# atum.net
KiCad netlist of a schematic drawn in EAGLE
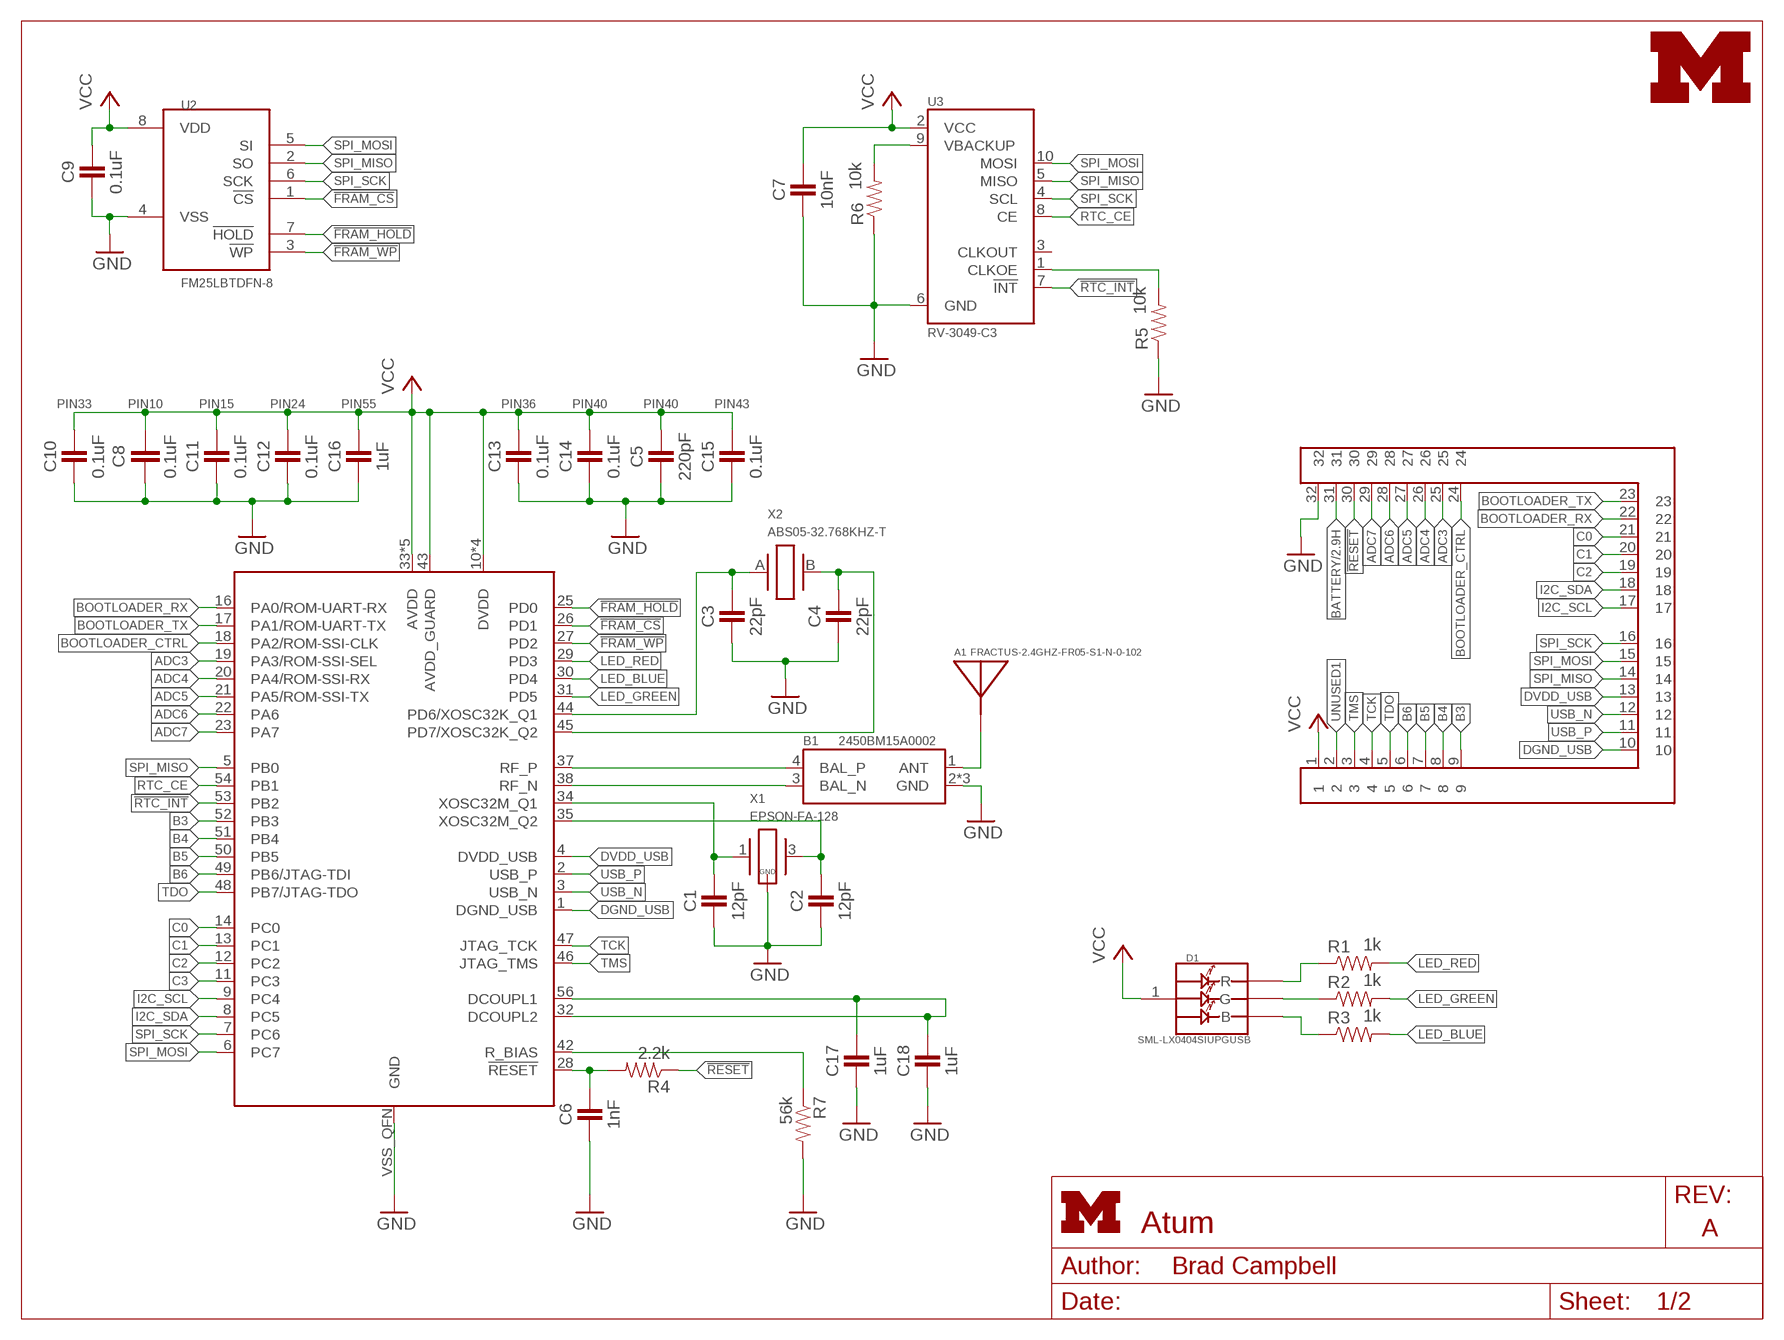
[diagram p0: schematic, sheet 1]
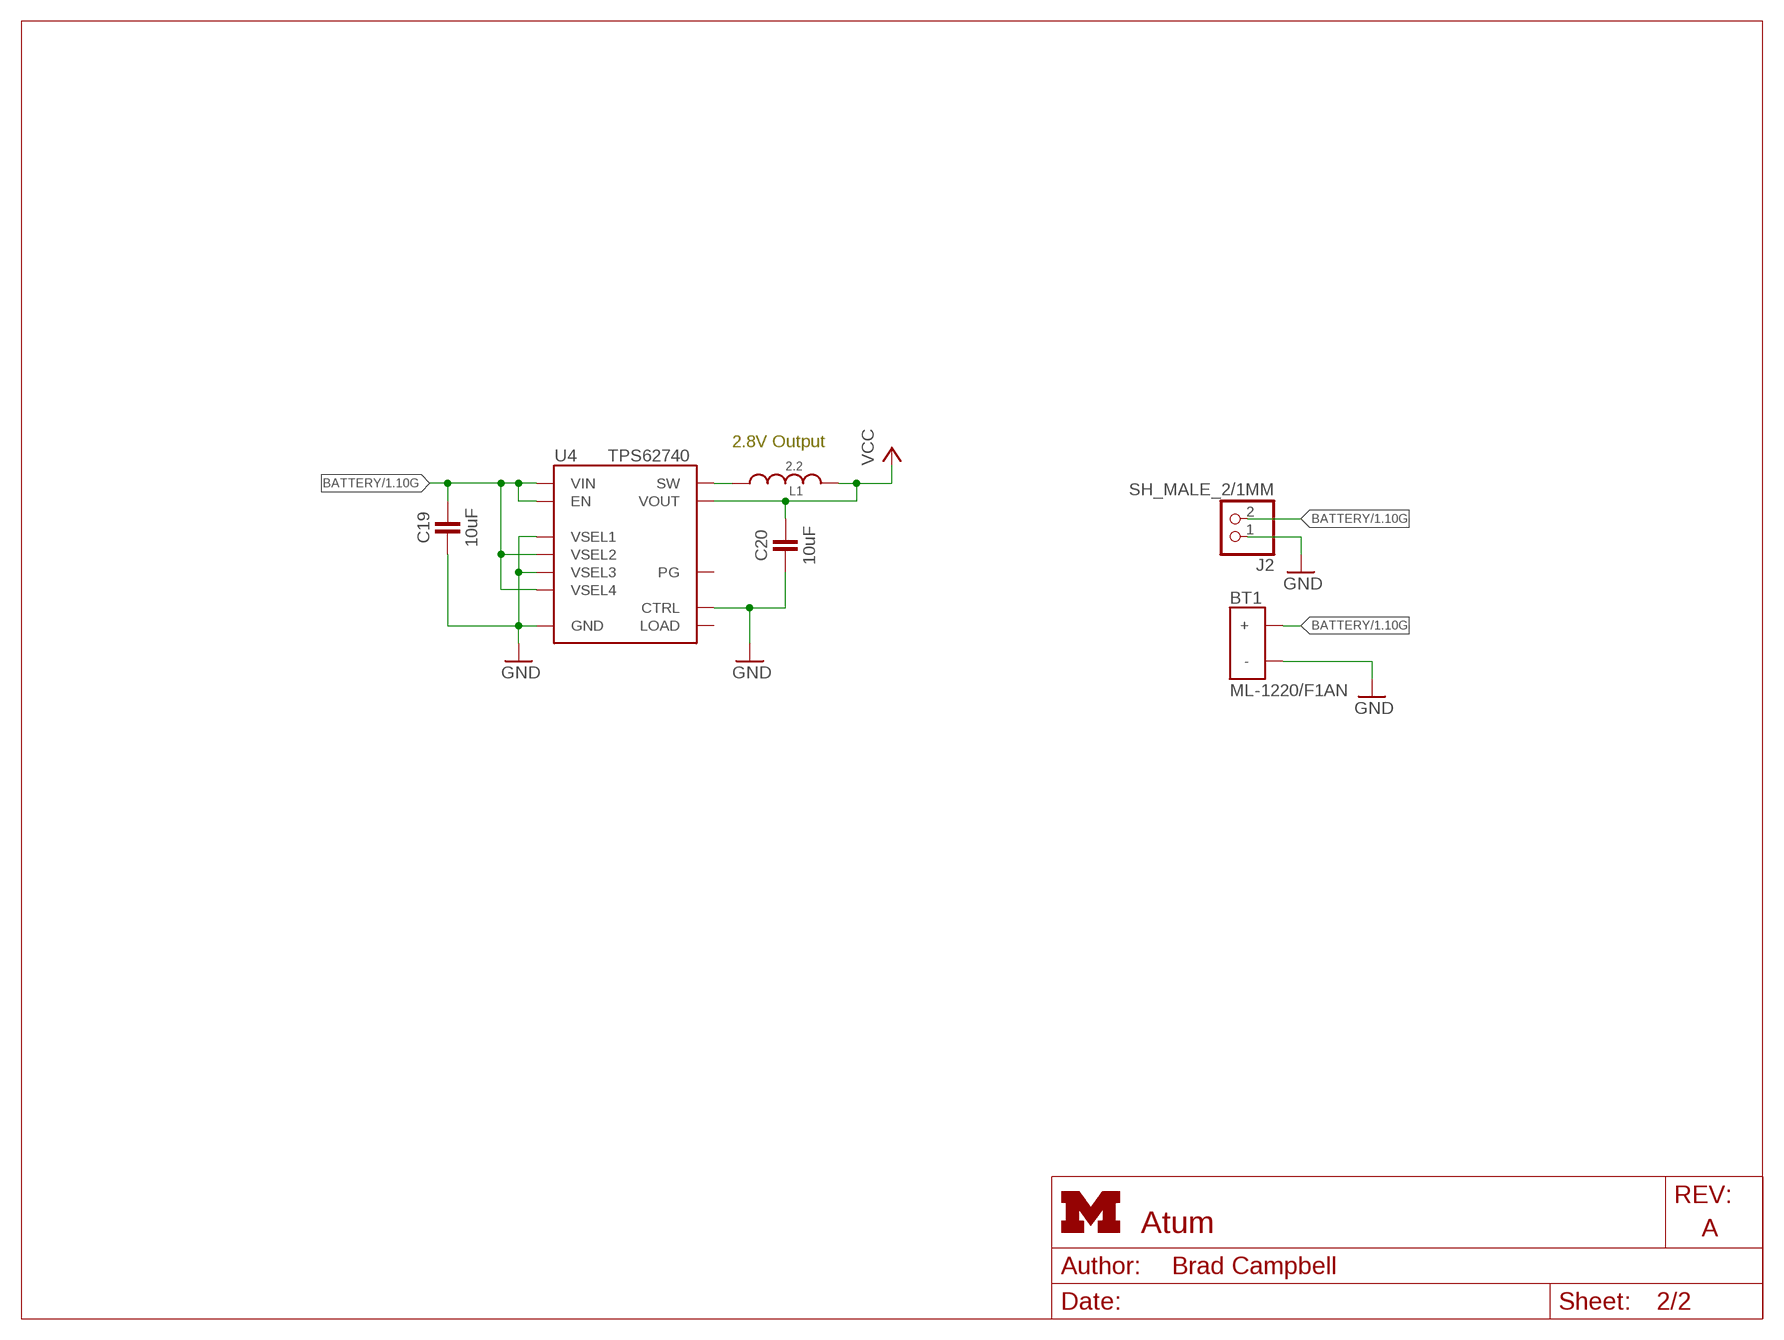
[diagram p1: schematic, sheet 2]

(export (version "E")
  (design (tool "Eeschema 10.0.6"))
  (components
    (comp (ref "A1")
      (value "FRACTUS-2.4GHZ-FR05-S1-N-0-102")
      (footprint "eagle-import:FRACTUS-ANTENNA-FR05-S1-N-0-102")
      (libsource (lib "eagle-import") (part "FRACTUS-2.4GHZ-FR05-S1-N-0-102"))
    )
    (comp (ref "B1")
      (value "2450BM15A0002")
      (footprint "eagle-import:2450BM")
      (libsource (lib "eagle-import") (part "2450BM15A0002"))
    )
    (comp (ref "C1")
      (value "12pF")
      (footprint "eagle-import:0402_CAP")
      (libsource (lib "eagle-import") (part "CAPACITOR"))
    )
    (comp (ref "C2")
      (value "12pF")
      (footprint "eagle-import:0402_CAP")
      (libsource (lib "eagle-import") (part "CAPACITOR"))
    )
    (comp (ref "C3")
      (value "22pF")
      (footprint "eagle-import:0402_CAP")
      (libsource (lib "eagle-import") (part "CAPACITOR"))
    )
    (comp (ref "C4")
      (value "22pF")
      (footprint "eagle-import:0402_CAP")
      (libsource (lib "eagle-import") (part "CAPACITOR"))
    )
    (comp (ref "C5")
      (value "220pF")
      (footprint "eagle-import:0402_CAP")
      (libsource (lib "eagle-import") (part "CAPACITOR"))
    )
    (comp (ref "C6")
      (value "1nF")
      (footprint "eagle-import:0402_CAP")
      (libsource (lib "eagle-import") (part "CAPACITOR"))
    )
    (comp (ref "C7")
      (value "10nF")
      (footprint "eagle-import:0402_CAP")
      (libsource (lib "eagle-import") (part "CAPACITOR"))
    )
    (comp (ref "C8")
      (value "0.1uF")
      (footprint "eagle-import:C0201")
      (libsource (lib "eagle-import") (part "C-EUC0201"))
    )
    (comp (ref "C9")
      (value "0.1uF")
      (footprint "eagle-import:0402_CAP")
      (libsource (lib "eagle-import") (part "CAPACITOR"))
    )
    (comp (ref "C10")
      (value "0.1uF")
      (footprint "eagle-import:0402_CAP")
      (libsource (lib "eagle-import") (part "CAPACITOR"))
    )
    (comp (ref "C11")
      (value "0.1uF")
      (footprint "eagle-import:0402_CAP")
      (libsource (lib "eagle-import") (part "CAPACITOR"))
    )
    (comp (ref "C12")
      (value "0.1uF")
      (footprint "eagle-import:0402_CAP")
      (libsource (lib "eagle-import") (part "CAPACITOR"))
    )
    (comp (ref "C13")
      (value "0.1uF")
      (footprint "eagle-import:0402_CAP")
      (libsource (lib "eagle-import") (part "CAPACITOR"))
    )
    (comp (ref "C14")
      (value "0.1uF")
      (footprint "eagle-import:0402_CAP")
      (libsource (lib "eagle-import") (part "CAPACITOR"))
    )
    (comp (ref "C15")
      (value "0.1uF")
      (footprint "eagle-import:0402_CAP")
      (libsource (lib "eagle-import") (part "CAPACITOR"))
    )
    (comp (ref "C16")
      (value "1uF")
      (footprint "eagle-import:0402_CAP")
      (libsource (lib "eagle-import") (part "CAPACITOR"))
    )
    (comp (ref "C17")
      (value "1uF")
      (footprint "eagle-import:0402_CAP")
      (libsource (lib "eagle-import") (part "CAPACITOR"))
    )
    (comp (ref "C18")
      (value "1uF")
      (footprint "eagle-import:0402_CAP")
      (libsource (lib "eagle-import") (part "CAPACITOR"))
    )
    (comp (ref "D1")
      (value "SML-LX0404SIUPGUSB")
      (footprint "eagle-import:1MM_SQ_4PAD")
      (libsource (lib "eagle-import") (part "SML-LX0404SIUPGUSB"))
    )
    (comp (ref "J1")
      (value "EPIC2-HEADER2")
      (footprint "eagle-import:EPIC2-HEADER2")
      (libsource (lib "eagle-import") (part "EPIC2-HEADER2"))
    )
    (comp (ref "LOGO1")
      (value "UMICH_SOLID_TINY")
      (footprint "eagle-import:UMICH_SOLID_50MIL")
      (libsource (lib "eagle-import") (part "UMICH_SOLID_TINY"))
    )
    (comp (ref "R1")
      (value "1k")
      (footprint "eagle-import:0402_RES")
      (libsource (lib "eagle-import") (part "RESISTOR"))
    )
    (comp (ref "R2")
      (value "1k")
      (footprint "eagle-import:0402_RES")
      (libsource (lib "eagle-import") (part "RESISTOR"))
    )
    (comp (ref "R3")
      (value "1k")
      (footprint "eagle-import:0402_RES")
      (libsource (lib "eagle-import") (part "RESISTOR"))
    )
    (comp (ref "R4")
      (value "2.2k")
      (footprint "eagle-import:0402_RES")
      (libsource (lib "eagle-import") (part "RESISTOR"))
    )
    (comp (ref "R5")
      (value "10k")
      (footprint "eagle-import:0402_RES")
      (libsource (lib "eagle-import") (part "RESISTOR"))
    )
    (comp (ref "R6")
      (value "10k")
      (footprint "eagle-import:0402_RES")
      (libsource (lib "eagle-import") (part "RESISTOR"))
    )
    (comp (ref "R7")
      (value "56k")
      (footprint "eagle-import:0402_RES")
      (libsource (lib "eagle-import") (part "RESISTOR"))
    )
    (comp (ref "U1")
      (value "CC2538")
      (footprint "eagle-import:S-PVQFN-N56")
      (libsource (lib "eagle-import") (part "CC2538"))
    )
    (comp (ref "U2")
      (value "FM25LBTDFN-8")
      (footprint "eagle-import:TDFN-8")
      (libsource (lib "eagle-import") (part "FM25LBTDFN-8"))
    )
    (comp (ref "U3")
      (value "RV-3049-C3")
      (footprint "eagle-import:MICRO-CRYSTAL-C3")
      (libsource (lib "eagle-import") (part "RV-3049-C3"))
    )
    (comp (ref "X1")
      (value "EPSON-FA-128")
      (footprint "eagle-import:FA-128")
      (libsource (lib "eagle-import") (part "EPSON-FA-128"))
    )
    (comp (ref "X2")
      (value "ABS05-32.768KHZ-T")
      (footprint "eagle-import:ABS05")
      (libsource (lib "eagle-import") (part "ABS05-32.768KHZ-T"))
    )
    (comp (ref "BT1")
      (value "ML-1220/F1AN")
      (footprint "eagle-import:ML-1220_F1BN")
      (libsource (lib "eagle-import") (part "ML-1220/F1AN"))
    )
    (comp (ref "C19")
      (value "10uF")
      (footprint "eagle-import:0603_CAP")
      (libsource (lib "eagle-import") (part "CAPACITOR0603_CAP"))
    )
    (comp (ref "C20")
      (value "10uF")
      (footprint "eagle-import:0603_CAP")
      (libsource (lib "eagle-import") (part "CAPACITOR0603_CAP"))
    )
    (comp (ref "J2")
      (value "SH_MALE_2/1MM")
      (footprint "eagle-import:SH-1X2_1MM")
      (libsource (lib "eagle-import") (part "SH_MALE_2/1MM"))
    )
    (comp (ref "L1")
      (value "2.2")
      (footprint "eagle-import:MIPSZ201D")
      (libsource (lib "eagle-import") (part "MIPSZ2012D"))
    )
    (comp (ref "U4")
      (value "TPS62740")
      (footprint "eagle-import:R-PWSON-12")
      (libsource (lib "eagle-import") (part "TPS62740"))
    )
  )
  (nets
    (net (code "1") (name "ADC3") (class "Default")
      (node (ref "J1") (pin "25") (pinfunction "25_25") (pintype "bidirectional"))
      (node (ref "U1") (pin "19") (pinfunction "PA3/ROM-SSI-SEL_19") (pintype "bidirectional"))
    )
    (net (code "2") (name "ADC4") (class "Default")
      (node (ref "J1") (pin "26") (pinfunction "26_26") (pintype "bidirectional"))
      (node (ref "U1") (pin "20") (pinfunction "PA4/ROM-SSI-RX_20") (pintype "bidirectional"))
    )
    (net (code "3") (name "ADC5") (class "Default")
      (node (ref "J1") (pin "27") (pinfunction "27_27") (pintype "bidirectional"))
      (node (ref "U1") (pin "21") (pinfunction "PA5/ROM-SSI-TX_21") (pintype "bidirectional"))
    )
    (net (code "4") (name "ADC6") (class "Default")
      (node (ref "J1") (pin "28") (pinfunction "28_28") (pintype "bidirectional"))
      (node (ref "U1") (pin "22") (pinfunction "PA6_22") (pintype "bidirectional"))
    )
    (net (code "5") (name "ADC7") (class "Default")
      (node (ref "J1") (pin "29") (pinfunction "29_29") (pintype "bidirectional"))
      (node (ref "U1") (pin "23") (pinfunction "PA7_23") (pintype "bidirectional"))
    )
    (net (code "6") (name "B3") (class "Default")
      (node (ref "J1") (pin "9") (pinfunction "9_9") (pintype "bidirectional"))
      (node (ref "U1") (pin "52") (pinfunction "PB3_52") (pintype "bidirectional"))
    )
    (net (code "7") (name "B4") (class "Default")
      (node (ref "J1") (pin "8") (pinfunction "8_8") (pintype "bidirectional"))
      (node (ref "U1") (pin "51") (pinfunction "PB4_51") (pintype "bidirectional"))
    )
    (net (code "8") (name "B5") (class "Default")
      (node (ref "J1") (pin "7") (pinfunction "7_7") (pintype "bidirectional"))
      (node (ref "U1") (pin "50") (pinfunction "PB5_50") (pintype "bidirectional"))
    )
    (net (code "9") (name "B6") (class "Default")
      (node (ref "J1") (pin "6") (pinfunction "6_6") (pintype "bidirectional"))
      (node (ref "U1") (pin "49") (pinfunction "PB6/JTAG-TDI_49") (pintype "bidirectional"))
    )
    (net (code "10") (name "BATTERY") (class "Default")
      (node (ref "BT1") (pin "POS") (pinfunction "+_POS") (pintype "bidirectional"))
      (node (ref "C19") (pin "1") (pinfunction "1_1") (pintype "bidirectional"))
      (node (ref "J1") (pin "31") (pinfunction "31_31") (pintype "bidirectional"))
      (node (ref "J2") (pin "2") (pinfunction "2_2") (pintype "passive"))
      (node (ref "U4") (pin "1") (pinfunction "VIN_1") (pintype "bidirectional"))
      (node (ref "U4") (pin "10") (pinfunction "VSEL2_10") (pintype "bidirectional"))
      (node (ref "U4") (pin "12") (pinfunction "EN_12") (pintype "bidirectional"))
      (node (ref "U4") (pin "8") (pinfunction "VSEL4_8") (pintype "bidirectional"))
    )
    (net (code "11") (name "BOOTLOADER_CTRL") (class "Default")
      (node (ref "J1") (pin "24") (pinfunction "24_24") (pintype "bidirectional"))
      (node (ref "U1") (pin "18") (pinfunction "PA2/ROM-SSI-CLK_18") (pintype "bidirectional"))
    )
    (net (code "12") (name "BOOTLOADER_RX") (class "Default")
      (node (ref "J1") (pin "22") (pinfunction "22_22") (pintype "bidirectional"))
      (node (ref "U1") (pin "16") (pinfunction "PA0/ROM-UART-RX_16") (pintype "bidirectional"))
    )
    (net (code "13") (name "BOOTLOADER_TX") (class "Default")
      (node (ref "J1") (pin "23") (pinfunction "23_23") (pintype "bidirectional"))
      (node (ref "U1") (pin "17") (pinfunction "PA1/ROM-UART-TX_17") (pintype "bidirectional"))
    )
    (net (code "14") (name "C0") (class "Default")
      (node (ref "J1") (pin "21") (pinfunction "21_21") (pintype "bidirectional"))
      (node (ref "U1") (pin "14") (pinfunction "PC0_14") (pintype "bidirectional"))
    )
    (net (code "15") (name "C1") (class "Default")
      (node (ref "J1") (pin "20") (pinfunction "20_20") (pintype "bidirectional"))
      (node (ref "U1") (pin "13") (pinfunction "PC1_13") (pintype "bidirectional"))
    )
    (net (code "16") (name "C2") (class "Default")
      (node (ref "J1") (pin "19") (pinfunction "19_19") (pintype "bidirectional"))
      (node (ref "U1") (pin "12") (pinfunction "PC2_12") (pintype "bidirectional"))
    )
    (net (code "17") (name "C3") (class "Default")
      (node (ref "U1") (pin "11") (pinfunction "PC3_11") (pintype "bidirectional"))
    )
    (net (code "18") (name "DGND_USB") (class "Default")
      (node (ref "J1") (pin "10") (pinfunction "10_10") (pintype "bidirectional"))
      (node (ref "U1") (pin "1") (pinfunction "DGND_USB_1") (pintype "bidirectional"))
    )
    (net (code "19") (name "DVDD_USB") (class "Default")
      (node (ref "J1") (pin "13") (pinfunction "13_13") (pintype "bidirectional"))
      (node (ref "U1") (pin "4") (pinfunction "DVDD_USB_4") (pintype "bidirectional"))
    )
    (net (code "20") (name "GND") (class "Default")
      (node (ref "B1") (pin "2") (pinfunction "GND_2") (pintype "bidirectional"))
      (node (ref "B1") (pin "5") (pinfunction "GND_5") (pintype "bidirectional"))
      (node (ref "B1") (pin "6") (pinfunction "GND_6") (pintype "bidirectional"))
      (node (ref "BT1") (pin "NEG") (pinfunction "-_NEG") (pintype "bidirectional"))
      (node (ref "C1") (pin "2") (pinfunction "2_2") (pintype "bidirectional"))
      (node (ref "C10") (pin "2") (pinfunction "2_2") (pintype "bidirectional"))
      (node (ref "C11") (pin "2") (pinfunction "2_2") (pintype "bidirectional"))
      (node (ref "C12") (pin "2") (pinfunction "2_2") (pintype "bidirectional"))
      (node (ref "C13") (pin "2") (pinfunction "2_2") (pintype "bidirectional"))
      (node (ref "C14") (pin "2") (pinfunction "2_2") (pintype "bidirectional"))
      (node (ref "C15") (pin "2") (pinfunction "2_2") (pintype "bidirectional"))
      (node (ref "C16") (pin "2") (pinfunction "2_2") (pintype "bidirectional"))
      (node (ref "C17") (pin "2") (pinfunction "2_2") (pintype "bidirectional"))
      (node (ref "C18") (pin "2") (pinfunction "2_2") (pintype "bidirectional"))
      (node (ref "C19") (pin "2") (pinfunction "2_2") (pintype "bidirectional"))
      (node (ref "C2") (pin "2") (pinfunction "2_2") (pintype "bidirectional"))
      (node (ref "C20") (pin "2") (pinfunction "2_2") (pintype "bidirectional"))
      (node (ref "C3") (pin "2") (pinfunction "2_2") (pintype "bidirectional"))
      (node (ref "C4") (pin "2") (pinfunction "2_2") (pintype "bidirectional"))
      (node (ref "C5") (pin "2") (pinfunction "2_2") (pintype "bidirectional"))
      (node (ref "C6") (pin "2") (pinfunction "2_2") (pintype "bidirectional"))
      (node (ref "C7") (pin "2") (pinfunction "2_2") (pintype "bidirectional"))
      (node (ref "C8") (pin "2") (pinfunction "2_2") (pintype "passive"))
      (node (ref "C9") (pin "2") (pinfunction "2_2") (pintype "bidirectional"))
      (node (ref "J1") (pin "32") (pinfunction "32_32") (pintype "bidirectional"))
      (node (ref "J2") (pin "1") (pinfunction "1_1") (pintype "passive"))
      (node (ref "R5") (pin "1") (pinfunction "1_1") (pintype "passive"))
      (node (ref "R6") (pin "1") (pinfunction "1_1") (pintype "passive"))
      (node (ref "R7") (pin "2") (pinfunction "2_2") (pintype "passive"))
      (node (ref "U1") (pin "VSS_QFN") (pinfunction "GND_VSS_QFN") (pintype "bidirectional"))
      (node (ref "U2") (pin "4") (pinfunction "VSS_4") (pintype "bidirectional"))
      (node (ref "U3") (pin "6") (pinfunction "GND_6") (pintype "bidirectional"))
      (node (ref "U4") (pin "11") (pinfunction "VSEL1_11") (pintype "bidirectional"))
      (node (ref "U4") (pin "3") (pinfunction "GND_3") (pintype "bidirectional"))
      (node (ref "U4") (pin "4") (pinfunction "CTRL_4") (pintype "bidirectional"))
      (node (ref "U4") (pin "9") (pinfunction "VSEL3_9") (pintype "bidirectional"))
      (node (ref "U4") (pin "NC") (pinfunction "GND_NC") (pintype "bidirectional"))
      (node (ref "X1") (pin "2") (pinfunction "GND_2") (pintype "bidirectional"))
      (node (ref "X1") (pin "4") (pinfunction "GND_4") (pintype "bidirectional"))
    )
    (net (code "21") (name "I2C_SCL") (class "Default")
      (node (ref "J1") (pin "17") (pinfunction "17_17") (pintype "bidirectional"))
      (node (ref "U1") (pin "9") (pinfunction "PC4_9") (pintype "bidirectional"))
    )
    (net (code "22") (name "I2C_SDA") (class "Default")
      (node (ref "J1") (pin "18") (pinfunction "18_18") (pintype "bidirectional"))
      (node (ref "U1") (pin "8") (pinfunction "PC5_8") (pintype "bidirectional"))
    )
    (net (code "23") (name "LED_BLUE") (class "Default")
      (node (ref "R3") (pin "2") (pinfunction "2_2") (pintype "passive"))
      (node (ref "U1") (pin "30") (pinfunction "PD4_30") (pintype "bidirectional"))
    )
    (net (code "24") (name "LED_GREEN") (class "Default")
      (node (ref "R2") (pin "2") (pinfunction "2_2") (pintype "passive"))
      (node (ref "U1") (pin "31") (pinfunction "PD5_31") (pintype "bidirectional"))
    )
    (net (code "25") (name "LED_RED") (class "Default")
      (node (ref "R1") (pin "2") (pinfunction "2_2") (pintype "passive"))
      (node (ref "U1") (pin "29") (pinfunction "PD3_29") (pintype "bidirectional"))
    )
    (net (code "26") (name "Net-(A1-ANTENNA)") (class "Default")
      (node (ref "A1") (pin "1") (pinfunction "ANTENNA_1") (pintype "bidirectional"))
      (node (ref "B1") (pin "1") (pinfunction "ANT_1") (pintype "bidirectional"))
    )
    (net (code "27") (name "Net-(B1-BAL_N)") (class "Default")
      (node (ref "B1") (pin "3") (pinfunction "BAL_N_3") (pintype "bidirectional"))
      (node (ref "U1") (pin "38") (pinfunction "RF_N_38") (pintype "bidirectional"))
    )
    (net (code "28") (name "Net-(B1-BAL_P)") (class "Default")
      (node (ref "B1") (pin "4") (pinfunction "BAL_P_4") (pintype "bidirectional"))
      (node (ref "U1") (pin "37") (pinfunction "RF_P_37") (pintype "bidirectional"))
    )
    (net (code "29") (name "Net-(D1-B)") (class "Default")
      (node (ref "D1") (pin "3") (pinfunction "B_3") (pintype "output"))
      (node (ref "R3") (pin "1") (pinfunction "1_1") (pintype "passive"))
    )
    (net (code "30") (name "Net-(D1-G)") (class "Default")
      (node (ref "D1") (pin "4") (pinfunction "G_4") (pintype "output"))
      (node (ref "R2") (pin "1") (pinfunction "1_1") (pintype "passive"))
    )
    (net (code "31") (name "Net-(D1-R)") (class "Default")
      (node (ref "D1") (pin "2") (pinfunction "R_2") (pintype "output"))
      (node (ref "R1") (pin "1") (pinfunction "1_1") (pintype "passive"))
    )
    (net (code "32") (name "Net-(U1-DCOUPL1)") (class "Default")
      (node (ref "C17") (pin "1") (pinfunction "1_1") (pintype "bidirectional"))
      (node (ref "C18") (pin "1") (pinfunction "1_1") (pintype "bidirectional"))
      (node (ref "U1") (pin "32") (pinfunction "DCOUPL2_32") (pintype "bidirectional"))
      (node (ref "U1") (pin "56") (pinfunction "DCOUPL1_56") (pintype "bidirectional"))
    )
    (net (code "33") (name "Net-(U1-PD6{slash}XOSC32K_Q1)") (class "Default")
      (node (ref "C3") (pin "1") (pinfunction "1_1") (pintype "bidirectional"))
      (node (ref "U1") (pin "44") (pinfunction "PD6/XOSC32K_Q1_44") (pintype "bidirectional"))
      (node (ref "X2") (pin "A") (pinfunction "1_A") (pintype "bidirectional"))
    )
    (net (code "34") (name "Net-(U1-PD7{slash}XOSC32K_Q2)") (class "Default")
      (node (ref "C4") (pin "1") (pinfunction "1_1") (pintype "bidirectional"))
      (node (ref "U1") (pin "45") (pinfunction "PD7/XOSC32K_Q2_45") (pintype "bidirectional"))
      (node (ref "X2") (pin "B") (pinfunction "2_B") (pintype "bidirectional"))
    )
    (net (code "35") (name "Net-(U1-R_BIAS)") (class "Default")
      (node (ref "R7") (pin "1") (pinfunction "1_1") (pintype "passive"))
      (node (ref "U1") (pin "42") (pinfunction "R_BIAS_42") (pintype "bidirectional"))
    )
    (net (code "36") (name "Net-(U1-XOSC32M_Q1)") (class "Default")
      (node (ref "C1") (pin "1") (pinfunction "1_1") (pintype "bidirectional"))
      (node (ref "U1") (pin "34") (pinfunction "XOSC32M_Q1_34") (pintype "bidirectional"))
      (node (ref "X1") (pin "1") (pinfunction "1_1") (pintype "bidirectional"))
    )
    (net (code "37") (name "Net-(U1-XOSC32M_Q2)") (class "Default")
      (node (ref "C2") (pin "1") (pinfunction "1_1") (pintype "bidirectional"))
      (node (ref "U1") (pin "35") (pinfunction "XOSC32M_Q2_35") (pintype "bidirectional"))
      (node (ref "X1") (pin "3") (pinfunction "2_3") (pintype "bidirectional"))
    )
    (net (code "38") (name "Net-(U1-~{RESET})") (class "Default")
      (node (ref "C6") (pin "1") (pinfunction "1_1") (pintype "bidirectional"))
      (node (ref "R4") (pin "2") (pinfunction "2_2") (pintype "passive"))
      (node (ref "U1") (pin "28") (pinfunction "~{RESET}_28") (pintype "bidirectional"))
    )
    (net (code "39") (name "Net-(U3-CLKOE)") (class "Default")
      (node (ref "R5") (pin "2") (pinfunction "2_2") (pintype "passive"))
      (node (ref "U3") (pin "1") (pinfunction "CLKOE_1") (pintype "bidirectional"))
    )
    (net (code "40") (name "Net-(U3-VBACKUP)") (class "Default")
      (node (ref "R6") (pin "2") (pinfunction "2_2") (pintype "passive"))
      (node (ref "U3") (pin "9") (pinfunction "VBACKUP_9") (pintype "bidirectional"))
    )
    (net (code "41") (name "Net-(U4-SW)") (class "Default")
      (node (ref "L1") (pin "1") (pinfunction "1_1") (pintype "bidirectional"))
      (node (ref "U4") (pin "2") (pinfunction "SW_2") (pintype "bidirectional"))
    )
    (net (code "42") (name "RTC_CE") (class "Default")
      (node (ref "U1") (pin "54") (pinfunction "PB1_54") (pintype "bidirectional"))
      (node (ref "U3") (pin "8") (pinfunction "CE_8") (pintype "bidirectional"))
    )
    (net (code "43") (name "SPI_MISO") (class "Default")
      (node (ref "J1") (pin "14") (pinfunction "14_14") (pintype "bidirectional"))
      (node (ref "U1") (pin "5") (pinfunction "PB0_5") (pintype "bidirectional"))
      (node (ref "U2") (pin "2") (pinfunction "SO_2") (pintype "bidirectional"))
      (node (ref "U3") (pin "5") (pinfunction "MISO_5") (pintype "bidirectional"))
    )
    (net (code "44") (name "SPI_MOSI") (class "Default")
      (node (ref "J1") (pin "15") (pinfunction "15_15") (pintype "bidirectional"))
      (node (ref "U1") (pin "6") (pinfunction "PC7_6") (pintype "bidirectional"))
      (node (ref "U2") (pin "5") (pinfunction "SI_5") (pintype "bidirectional"))
      (node (ref "U3") (pin "10") (pinfunction "MOSI_10") (pintype "bidirectional"))
    )
    (net (code "45") (name "SPI_SCK") (class "Default")
      (node (ref "J1") (pin "16") (pinfunction "16_16") (pintype "bidirectional"))
      (node (ref "U1") (pin "7") (pinfunction "PC6_7") (pintype "bidirectional"))
      (node (ref "U2") (pin "6") (pinfunction "SCK_6") (pintype "bidirectional"))
      (node (ref "U3") (pin "4") (pinfunction "SCL_4") (pintype "bidirectional"))
    )
    (net (code "46") (name "TCK") (class "Default")
      (node (ref "J1") (pin "4") (pinfunction "4_4") (pintype "bidirectional"))
      (node (ref "U1") (pin "47") (pinfunction "JTAG_TCK_47") (pintype "bidirectional"))
    )
    (net (code "47") (name "TDO") (class "Default")
      (node (ref "J1") (pin "5") (pinfunction "5_5") (pintype "bidirectional"))
      (node (ref "U1") (pin "48") (pinfunction "PB7/JTAG-TDO_48") (pintype "bidirectional"))
    )
    (net (code "48") (name "TMS") (class "Default")
      (node (ref "J1") (pin "3") (pinfunction "3_3") (pintype "bidirectional"))
      (node (ref "U1") (pin "46") (pinfunction "JTAG_TMS_46") (pintype "bidirectional"))
    )
    (net (code "49") (name "UNUSED1") (class "Default")
      (node (ref "J1") (pin "2") (pinfunction "2_2") (pintype "bidirectional"))
    )
    (net (code "50") (name "USB_N") (class "Default")
      (node (ref "J1") (pin "12") (pinfunction "12_12") (pintype "bidirectional"))
      (node (ref "U1") (pin "3") (pinfunction "USB_N_3") (pintype "bidirectional"))
    )
    (net (code "51") (name "USB_P") (class "Default")
      (node (ref "J1") (pin "11") (pinfunction "11_11") (pintype "bidirectional"))
      (node (ref "U1") (pin "2") (pinfunction "USB_P_2") (pintype "bidirectional"))
    )
    (net (code "52") (name "VCC") (class "Default")
      (node (ref "C10") (pin "1") (pinfunction "1_1") (pintype "bidirectional"))
      (node (ref "C11") (pin "1") (pinfunction "1_1") (pintype "bidirectional"))
      (node (ref "C12") (pin "1") (pinfunction "1_1") (pintype "bidirectional"))
      (node (ref "C13") (pin "1") (pinfunction "1_1") (pintype "bidirectional"))
      (node (ref "C14") (pin "1") (pinfunction "1_1") (pintype "bidirectional"))
      (node (ref "C15") (pin "1") (pinfunction "1_1") (pintype "bidirectional"))
      (node (ref "C16") (pin "1") (pinfunction "1_1") (pintype "bidirectional"))
      (node (ref "C20") (pin "1") (pinfunction "1_1") (pintype "bidirectional"))
      (node (ref "C5") (pin "1") (pinfunction "1_1") (pintype "bidirectional"))
      (node (ref "C7") (pin "1") (pinfunction "1_1") (pintype "bidirectional"))
      (node (ref "C8") (pin "1") (pinfunction "1_1") (pintype "passive"))
      (node (ref "C9") (pin "1") (pinfunction "1_1") (pintype "bidirectional"))
      (node (ref "D1") (pin "1") (pinfunction "VDD_1") (pintype "bidirectional"))
      (node (ref "J1") (pin "1") (pinfunction "1_1") (pintype "bidirectional"))
      (node (ref "L1") (pin "2") (pinfunction "2_2") (pintype "bidirectional"))
      (node (ref "U1") (pin "10") (pinfunction "DVDD_10") (pintype "bidirectional"))
      (node (ref "U1") (pin "15") (pinfunction "DVDD_15") (pintype "bidirectional"))
      (node (ref "U1") (pin "24") (pinfunction "DVDD_24") (pintype "bidirectional"))
      (node (ref "U1") (pin "33") (pinfunction "AVDD_33") (pintype "bidirectional"))
      (node (ref "U1") (pin "36") (pinfunction "AVDD_36") (pintype "bidirectional"))
      (node (ref "U1") (pin "39") (pinfunction "AVDD_39") (pintype "bidirectional"))
      (node (ref "U1") (pin "40") (pinfunction "AVDD_40") (pintype "bidirectional"))
      (node (ref "U1") (pin "41") (pinfunction "AVDD_41") (pintype "bidirectional"))
      (node (ref "U1") (pin "43") (pinfunction "AVDD_GUARD_43") (pintype "bidirectional"))
      (node (ref "U1") (pin "55") (pinfunction "DVDD_55") (pintype "bidirectional"))
      (node (ref "U2") (pin "8") (pinfunction "VDD_8") (pintype "bidirectional"))
      (node (ref "U3") (pin "2") (pinfunction "VCC_2") (pintype "bidirectional"))
      (node (ref "U4") (pin "5") (pinfunction "VOUT_5") (pintype "bidirectional"))
    )
    (net (code "53") (name "unconnected-(U3-CLKOUT-Pad3)") (class "Default")
      (node (ref "U3") (pin "3") (pinfunction "CLKOUT_3") (pintype "bidirectional"))
    )
    (net (code "54") (name "unconnected-(U4-LOAD-Pad6)") (class "Default")
      (node (ref "U4") (pin "6") (pinfunction "LOAD_6") (pintype "bidirectional"))
    )
    (net (code "55") (name "unconnected-(U4-PG-Pad7)") (class "Default")
      (node (ref "U4") (pin "7") (pinfunction "PG_7") (pintype "bidirectional"))
    )
    (net (code "56") (name "~{FRAM_CS}") (class "Default")
      (node (ref "U1") (pin "26") (pinfunction "PD1_26") (pintype "bidirectional"))
      (node (ref "U2") (pin "1") (pinfunction "~{CS}_1") (pintype "bidirectional"))
    )
    (net (code "57") (name "~{FRAM_HOLD}") (class "Default")
      (node (ref "U1") (pin "25") (pinfunction "PD0_25") (pintype "bidirectional"))
      (node (ref "U2") (pin "7") (pinfunction "~{HOLD}_7") (pintype "bidirectional"))
    )
    (net (code "58") (name "~{FRAM_WP}") (class "Default")
      (node (ref "U1") (pin "27") (pinfunction "PD2_27") (pintype "bidirectional"))
      (node (ref "U2") (pin "3") (pinfunction "~{WP}_3") (pintype "bidirectional"))
    )
    (net (code "59") (name "~{RESET}") (class "Default")
      (node (ref "J1") (pin "30") (pinfunction "30_30") (pintype "bidirectional"))
      (node (ref "R4") (pin "1") (pinfunction "1_1") (pintype "passive"))
    )
    (net (code "60") (name "~{RTC_INT}") (class "Default")
      (node (ref "U1") (pin "53") (pinfunction "PB2_53") (pintype "bidirectional"))
      (node (ref "U3") (pin "7") (pinfunction "~{INT}_7") (pintype "bidirectional"))
    )
  )
)
